# Sheet3.net
KiCad netlist of a schematic drawn in Altium Designer
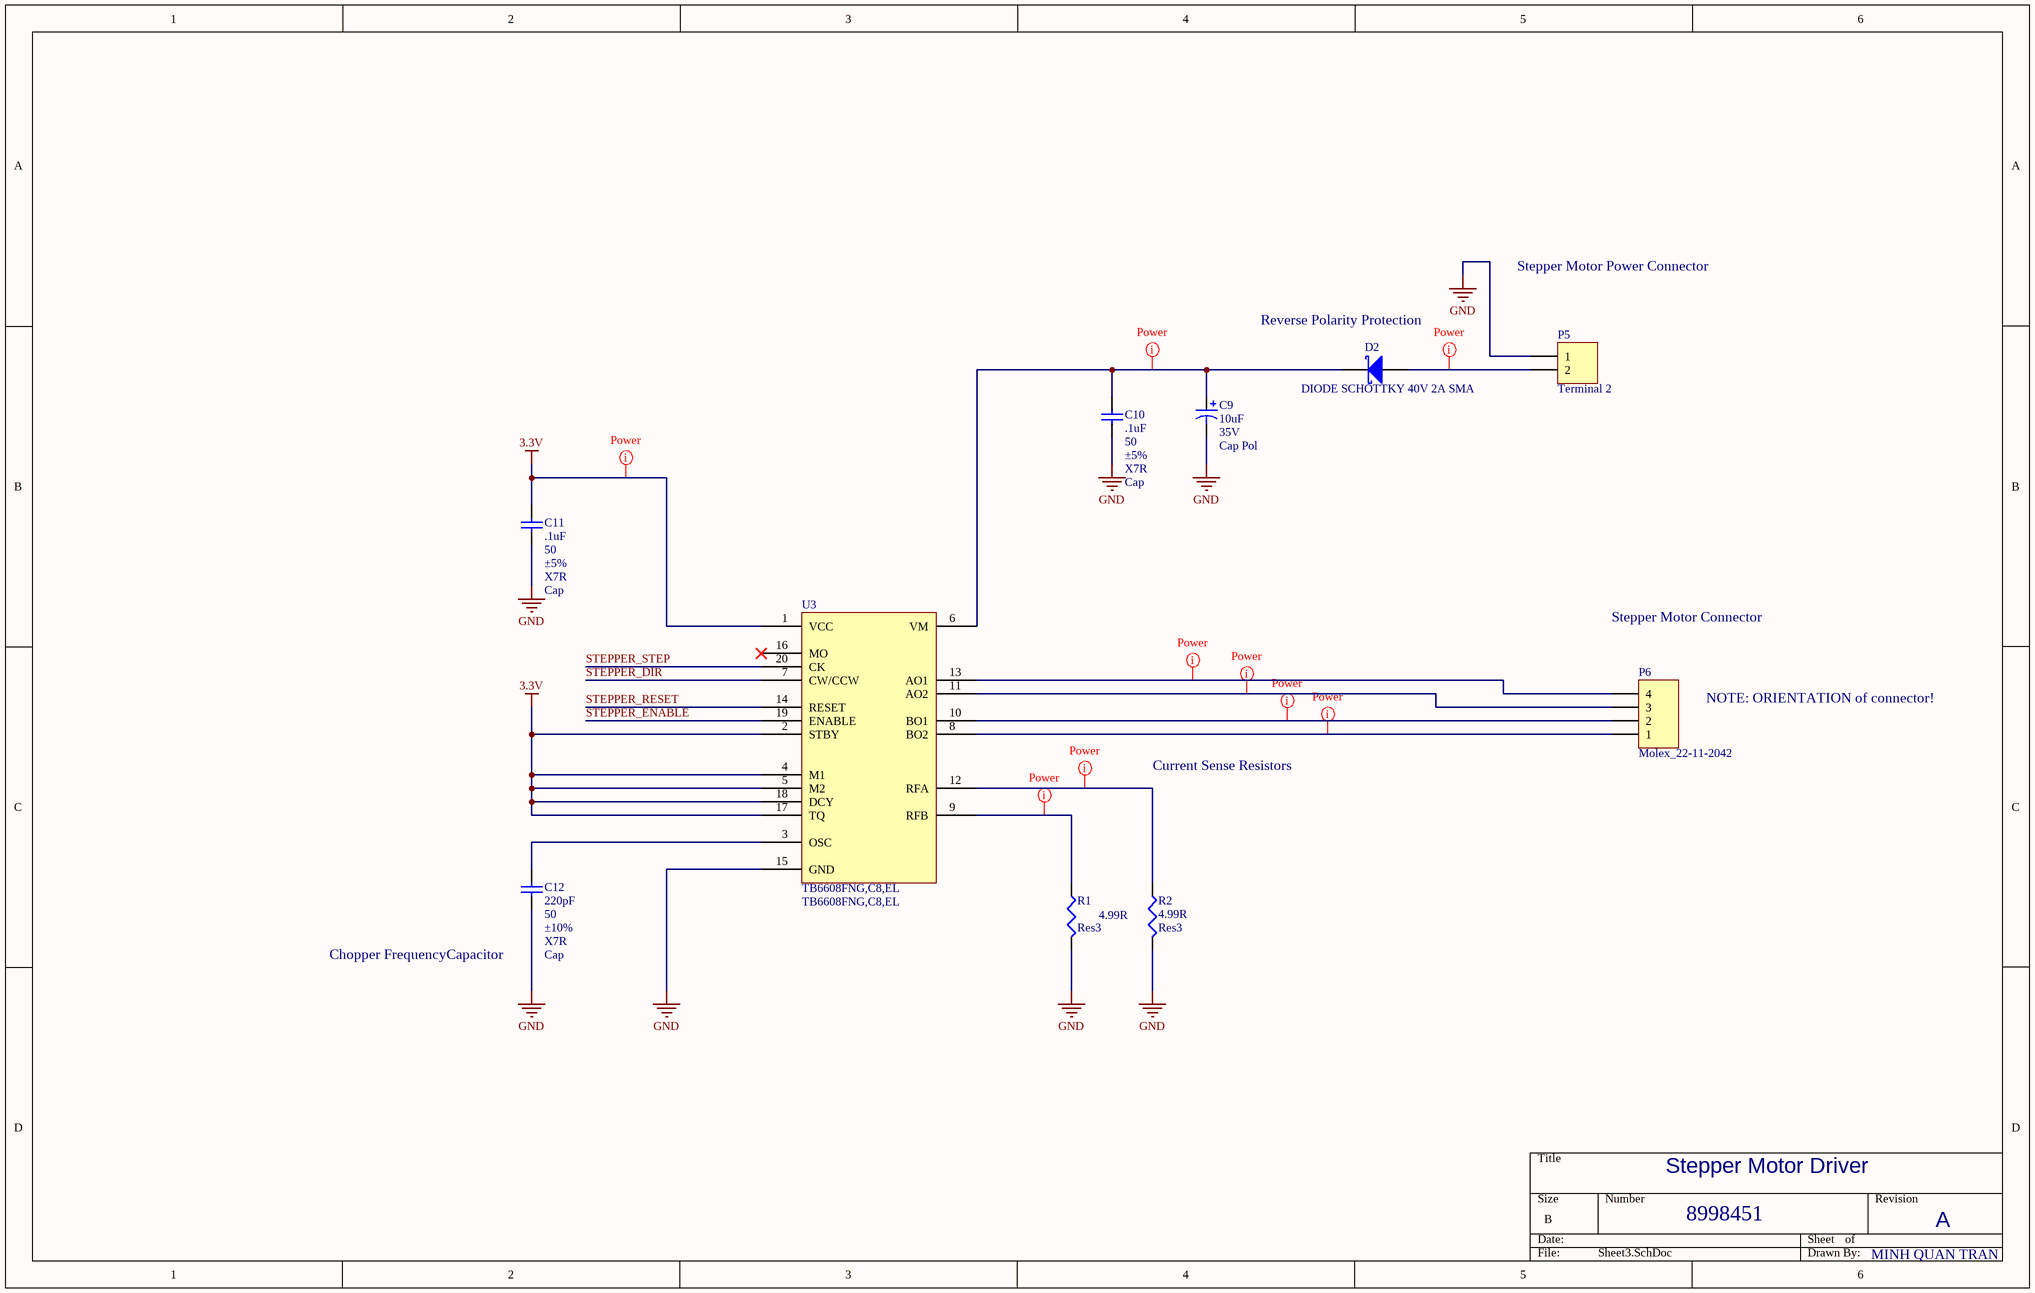
[diagram p0: Sheet3.SchDoc]

(export (version "E")
  (design (tool "Eeschema 10.0.6"))
  (components
    (comp (ref "C9")
      (value "Cap Pol")
      (footprint "CAPACITOR_5MM")
      (description "CAP 85C 10uF ±20% 35V WX Series Aluminum Electrolytic")
      (fields
        (field (name "ALTIUM_VALUE") "10uF")
        (field (name "VOLTAGE") "35V")
        (field (name "MPN") "UWX1V100MCL1GB")
      )
      (libsource (lib "esd_library") (part "Cap Polar-10uF-35V"))
    )
    (comp (ref "C10")
      (value "Cap")
      (footprint "CAPC2012X09M")
      (description "CAP CER .1uF 50v X7R 0805")
      (fields
        (field (name "ALTIUM_VALUE") ".1uF")
        (field (name "WV") "50")
        (field (name "TOLERANCE") "±5%")
        (field (name "TYPE") "X7R")
        (field (name "MPN") "C0805C104J5RACTU")
      )
      (libsource (lib "esd_library") (part "CAP-X7R-.1uF-50V-±5%"))
    )
    (comp (ref "C11")
      (value "Cap")
      (footprint "CAPC2012X09M")
      (description "CAP CER .1uF 50v X7R 0805")
      (fields
        (field (name "ALTIUM_VALUE") ".1uF")
        (field (name "WV") "50")
        (field (name "TOLERANCE") "±5%")
        (field (name "TYPE") "X7R")
        (field (name "MPN") "C0805C104J5RACTU")
      )
      (libsource (lib "esd_library") (part "CAP-X7R-.1uF-50V-±5%"))
    )
    (comp (ref "C12")
      (value "Cap")
      (footprint "CAPC2012X09M")
      (description "CAP CER 220pF 50v X7R 0805")
      (fields
        (field (name "ALTIUM_VALUE") "220pF")
        (field (name "WV") "50")
        (field (name "TOLERANCE") "±10%")
        (field (name "TYPE") "X7R")
        (field (name "MPN") "C0805C221K5RACTU")
      )
      (libsource (lib "esd_library") (part "CAP-X7R-220pF-50V-±10%"))
    )
    (comp (ref "D2")
      (value "DIODE SCHOTTKY 40V 2A SMA")
      (footprint "DIOM4326X23M")
      (description "Schottky Rectifier")
      (fields (field (name "MPN") "B240A-13-F"))
      (libsource (lib "esd_library") (part "DIODE SCHOTTKY 40V 2A SMA"))
    )
    (comp (ref "P5")
      (value "Terminal 2")
      (footprint "TYCO_282841_2")
      (description "Terminal, 2-Pin")
      (fields (field (name "MPN") "282841-2") (field (name "PUBLISHER") "Altium Limited"))
      (libsource (lib "esd_library") (part "Terminal 2"))
    )
    (comp (ref "P6")
      (value "Molex_22-11-2042")
      (footprint "MOLEX-22-11-2042")
      (description "CONN HEADER 4POS .100 VERT GOLD")
      (fields (field (name "MPN") "0022112042"))
      (libsource (lib "esd_library") (part "Molex_22-11-2042"))
    )
    (comp (ref "R1")
      (value "Res3")
      (footprint "RESC2112X05M")
      (description "RES SMD 4.99R OHM 1% 1/8W 0805")
      (fields (field (name "ALTIUM_VALUE") "4.99R") (field (name "MPN") "CRCW08054R99FKEA"))
      (libsource (lib "esd_library") (part "Resistor_4.99R"))
    )
    (comp (ref "R2")
      (value "Res3")
      (footprint "RESC2112X05M")
      (description "RES SMD 4.99R OHM 1% 1/8W 0805")
      (fields (field (name "ALTIUM_VALUE") "4.99R") (field (name "MPN") "CRCW08054R99FKEA"))
      (libsource (lib "esd_library") (part "Resistor_4.99R"))
    )
    (comp (ref "U3")
      (value "TB6608FNG,C8,EL")
      (footprint "TSOP65P640X160-20M")
      (description "IC MTR DRV BIPLR 2.7-5.5V 20SSOP")
      (fields (field (name "MPN") "TB6608FNG,C8,EL"))
      (libsource (lib "esd_library") (part "TB6608FNG,C8,EL"))
    )
  )
  (nets
    (net (code "1") (name "/STEPPER_DIR") (class "Default")
      (node (ref "U3") (pin "7") (pinfunction "CW/CCW_7") (pintype "passive"))
    )
    (net (code "2") (name "/STEPPER_ENABLE") (class "Default")
      (node (ref "U3") (pin "19") (pinfunction "ENABLE_19") (pintype "passive"))
    )
    (net (code "3") (name "/STEPPER_RESET") (class "Default")
      (node (ref "U3") (pin "14") (pinfunction "RESET_14") (pintype "passive"))
    )
    (net (code "4") (name "/STEPPER_STEP") (class "Default")
      (node (ref "U3") (pin "20") (pinfunction "CK_20") (pintype "passive"))
    )
    (net (code "5") (name "3.3V") (class "Default")
      (node (ref "C11") (pin "1") (pinfunction "1_1") (pintype "passive"))
      (node (ref "U3") (pin "1") (pinfunction "VCC_1") (pintype "passive"))
      (node (ref "U3") (pin "17") (pinfunction "TQ_17") (pintype "passive"))
      (node (ref "U3") (pin "18") (pinfunction "DCY_18") (pintype "passive"))
      (node (ref "U3") (pin "2") (pinfunction "STBY_2") (pintype "passive"))
      (node (ref "U3") (pin "4") (pinfunction "M1_4") (pintype "passive"))
      (node (ref "U3") (pin "5") (pinfunction "M2_5") (pintype "passive"))
    )
    (net (code "6") (name "GND") (class "Default")
      (node (ref "C10") (pin "1") (pinfunction "1_1") (pintype "passive"))
      (node (ref "C11") (pin "2") (pinfunction "2_2") (pintype "passive"))
      (node (ref "C12") (pin "2") (pinfunction "2_2") (pintype "passive"))
      (node (ref "C9") (pin "2") (pinfunction "2_2") (pintype "passive"))
      (node (ref "P5") (pin "1") (pinfunction "1_1") (pintype "passive"))
      (node (ref "R1") (pin "2") (pinfunction "2_2") (pintype "passive"))
      (node (ref "R2") (pin "2") (pinfunction "2_2") (pintype "passive"))
      (node (ref "U3") (pin "15") (pinfunction "GND_15") (pintype "passive"))
    )
    (net (code "7") (name "Net-(D2-A)") (class "Default")
      (node (ref "D2") (pin "2") (pinfunction "A_2") (pintype "passive"))
      (node (ref "P5") (pin "2") (pinfunction "2_2") (pintype "passive"))
    )
    (net (code "8") (name "Net-(D2-K)") (class "Default")
      (node (ref "C10") (pin "2") (pinfunction "2_2") (pintype "passive"))
      (node (ref "C9") (pin "1") (pinfunction "1_1") (pintype "passive"))
      (node (ref "D2") (pin "1") (pinfunction "K_1") (pintype "passive"))
      (node (ref "U3") (pin "6") (pinfunction "VM_6") (pintype "passive"))
    )
    (net (code "9") (name "Net-(U3-AO1)") (class "Default")
      (node (ref "P6") (pin "4") (pinfunction "4_4") (pintype "passive"))
      (node (ref "U3") (pin "13") (pinfunction "AO1_13") (pintype "passive"))
    )
    (net (code "10") (name "Net-(U3-AO2)") (class "Default")
      (node (ref "P6") (pin "3") (pinfunction "3_3") (pintype "passive"))
      (node (ref "U3") (pin "11") (pinfunction "AO2_11") (pintype "passive"))
    )
    (net (code "11") (name "Net-(U3-BO1)") (class "Default")
      (node (ref "P6") (pin "2") (pinfunction "2_2") (pintype "passive"))
      (node (ref "U3") (pin "10") (pinfunction "BO1_10") (pintype "passive"))
    )
    (net (code "12") (name "Net-(U3-BO2)") (class "Default")
      (node (ref "P6") (pin "1") (pinfunction "1_1") (pintype "passive"))
      (node (ref "U3") (pin "8") (pinfunction "BO2_8") (pintype "passive"))
    )
    (net (code "13") (name "Net-(U3-OSC)") (class "Default")
      (node (ref "C12") (pin "1") (pinfunction "1_1") (pintype "passive"))
      (node (ref "U3") (pin "3") (pinfunction "OSC_3") (pintype "passive"))
    )
    (net (code "14") (name "Net-(U3-RFA)") (class "Default")
      (node (ref "R2") (pin "1") (pinfunction "1_1") (pintype "passive"))
      (node (ref "U3") (pin "12") (pinfunction "RFA_12") (pintype "passive"))
    )
    (net (code "15") (name "Net-(U3-RFB)") (class "Default")
      (node (ref "R1") (pin "1") (pinfunction "1_1") (pintype "passive"))
      (node (ref "U3") (pin "9") (pinfunction "RFB_9") (pintype "passive"))
    )
    (net (code "16") (name "unconnected-(U3-MO-Pad16)") (class "Default")
      (node (ref "U3") (pin "16") (pinfunction "MO_16") (pintype "passive+no_connect"))
    )
  )
)
